# LEDARRAY.net
KiCad netlist of a schematic drawn in EAGLE
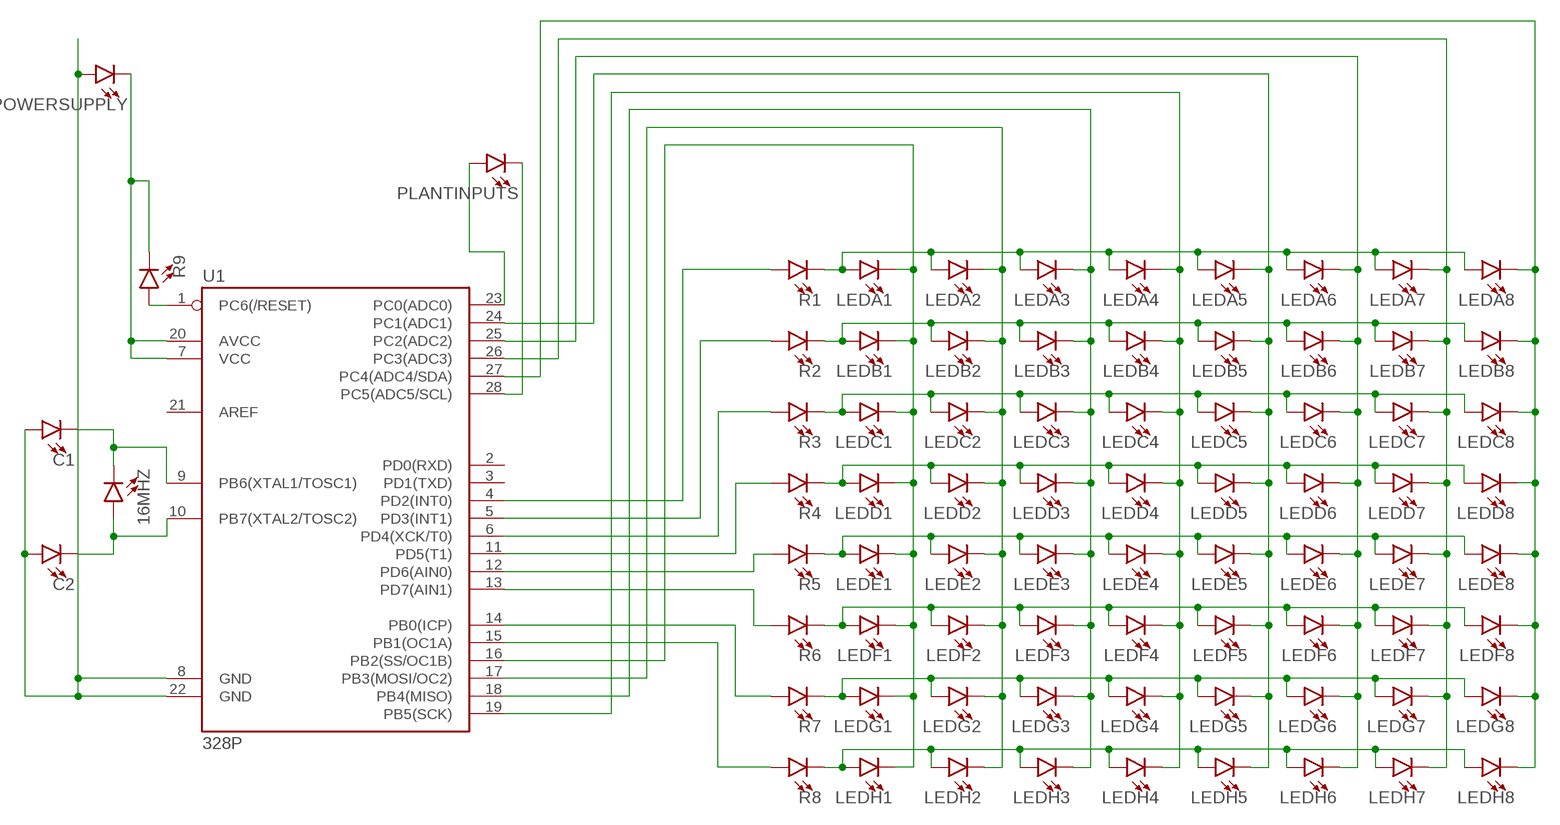
[diagram p0: schematic, sheet 1]

(export (version "E")
  (design (tool "Eeschema 10.0.6"))
  (components
    (comp (ref "16MHZ")
      (value "LED3MM")
      (footprint "eagle-import:LED_3MM")
      (libsource (lib "eagle-import") (part "LED3MM"))
    )
    (comp (ref "C1")
      (value "LED3MM")
      (footprint "eagle-import:LED_3MM")
      (libsource (lib "eagle-import") (part "LED3MM"))
    )
    (comp (ref "C2")
      (value "LED3MM")
      (footprint "eagle-import:LED_3MM")
      (libsource (lib "eagle-import") (part "LED3MM"))
    )
    (comp (ref "LEDA1")
      (value "LED3MM")
      (footprint "eagle-import:LED_3MM")
      (libsource (lib "eagle-import") (part "LED3MM"))
    )
    (comp (ref "LEDA2")
      (value "LED3MM")
      (footprint "eagle-import:LED_3MM")
      (libsource (lib "eagle-import") (part "LED3MM"))
    )
    (comp (ref "LEDA3")
      (value "LED3MM")
      (footprint "eagle-import:LED_3MM")
      (libsource (lib "eagle-import") (part "LED3MM"))
    )
    (comp (ref "LEDA4")
      (value "LED3MM")
      (footprint "eagle-import:LED_3MM")
      (libsource (lib "eagle-import") (part "LED3MM"))
    )
    (comp (ref "LEDA5")
      (value "LED3MM")
      (footprint "eagle-import:LED_3MM")
      (libsource (lib "eagle-import") (part "LED3MM"))
    )
    (comp (ref "LEDA6")
      (value "LED3MM")
      (footprint "eagle-import:LED_3MM")
      (libsource (lib "eagle-import") (part "LED3MM"))
    )
    (comp (ref "LEDA7")
      (value "LED3MM")
      (footprint "eagle-import:LED_3MM")
      (libsource (lib "eagle-import") (part "LED3MM"))
    )
    (comp (ref "LEDA8")
      (value "LED3MM")
      (footprint "eagle-import:LED_3MM")
      (libsource (lib "eagle-import") (part "LED3MM"))
    )
    (comp (ref "LEDB1")
      (value "LED3MM")
      (footprint "eagle-import:LED_3MM")
      (libsource (lib "eagle-import") (part "LED3MM"))
    )
    (comp (ref "LEDB2")
      (value "LED3MM")
      (footprint "eagle-import:LED_3MM")
      (libsource (lib "eagle-import") (part "LED3MM"))
    )
    (comp (ref "LEDB3")
      (value "LED3MM")
      (footprint "eagle-import:LED_3MM")
      (libsource (lib "eagle-import") (part "LED3MM"))
    )
    (comp (ref "LEDB4")
      (value "LED3MM")
      (footprint "eagle-import:LED_3MM")
      (libsource (lib "eagle-import") (part "LED3MM"))
    )
    (comp (ref "LEDB5")
      (value "LED3MM")
      (footprint "eagle-import:LED_3MM")
      (libsource (lib "eagle-import") (part "LED3MM"))
    )
    (comp (ref "LEDB6")
      (value "LED3MM")
      (footprint "eagle-import:LED_3MM")
      (libsource (lib "eagle-import") (part "LED3MM"))
    )
    (comp (ref "LEDB7")
      (value "LED3MM")
      (footprint "eagle-import:LED_3MM")
      (libsource (lib "eagle-import") (part "LED3MM"))
    )
    (comp (ref "LEDB8")
      (value "LED3MM")
      (footprint "eagle-import:LED_3MM")
      (libsource (lib "eagle-import") (part "LED3MM"))
    )
    (comp (ref "LEDC1")
      (value "LED3MM")
      (footprint "eagle-import:LED_3MM")
      (libsource (lib "eagle-import") (part "LED3MM"))
    )
    (comp (ref "LEDC2")
      (value "LED3MM")
      (footprint "eagle-import:LED_3MM")
      (libsource (lib "eagle-import") (part "LED3MM"))
    )
    (comp (ref "LEDC3")
      (value "LED3MM")
      (footprint "eagle-import:LED_3MM")
      (libsource (lib "eagle-import") (part "LED3MM"))
    )
    (comp (ref "LEDC4")
      (value "LED3MM")
      (footprint "eagle-import:LED_3MM")
      (libsource (lib "eagle-import") (part "LED3MM"))
    )
    (comp (ref "LEDC5")
      (value "LED3MM")
      (footprint "eagle-import:LED_3MM")
      (libsource (lib "eagle-import") (part "LED3MM"))
    )
    (comp (ref "LEDC6")
      (value "LED3MM")
      (footprint "eagle-import:LED_3MM")
      (libsource (lib "eagle-import") (part "LED3MM"))
    )
    (comp (ref "LEDC7")
      (value "LED3MM")
      (footprint "eagle-import:LED_3MM")
      (libsource (lib "eagle-import") (part "LED3MM"))
    )
    (comp (ref "LEDC8")
      (value "LED3MM")
      (footprint "eagle-import:LED_3MM")
      (libsource (lib "eagle-import") (part "LED3MM"))
    )
    (comp (ref "LEDD1")
      (value "LED3MM")
      (footprint "eagle-import:LED_3MM")
      (libsource (lib "eagle-import") (part "LED3MM"))
    )
    (comp (ref "LEDD2")
      (value "LED3MM")
      (footprint "eagle-import:LED_3MM")
      (libsource (lib "eagle-import") (part "LED3MM"))
    )
    (comp (ref "LEDD3")
      (value "LED3MM")
      (footprint "eagle-import:LED_3MM")
      (libsource (lib "eagle-import") (part "LED3MM"))
    )
    (comp (ref "LEDD4")
      (value "LED3MM")
      (footprint "eagle-import:LED_3MM")
      (libsource (lib "eagle-import") (part "LED3MM"))
    )
    (comp (ref "LEDD5")
      (value "LED3MM")
      (footprint "eagle-import:LED_3MM")
      (libsource (lib "eagle-import") (part "LED3MM"))
    )
    (comp (ref "LEDD6")
      (value "LED3MM")
      (footprint "eagle-import:LED_3MM")
      (libsource (lib "eagle-import") (part "LED3MM"))
    )
    (comp (ref "LEDD7")
      (value "LED3MM")
      (footprint "eagle-import:LED_3MM")
      (libsource (lib "eagle-import") (part "LED3MM"))
    )
    (comp (ref "LEDD8")
      (value "LED3MM")
      (footprint "eagle-import:LED_3MM")
      (libsource (lib "eagle-import") (part "LED3MM"))
    )
    (comp (ref "LEDE1")
      (value "LED3MM")
      (footprint "eagle-import:LED_3MM")
      (libsource (lib "eagle-import") (part "LED3MM"))
    )
    (comp (ref "LEDE2")
      (value "LED3MM")
      (footprint "eagle-import:LED_3MM")
      (libsource (lib "eagle-import") (part "LED3MM"))
    )
    (comp (ref "LEDE3")
      (value "LED3MM")
      (footprint "eagle-import:LED_3MM")
      (libsource (lib "eagle-import") (part "LED3MM"))
    )
    (comp (ref "LEDE4")
      (value "LED3MM")
      (footprint "eagle-import:LED_3MM")
      (libsource (lib "eagle-import") (part "LED3MM"))
    )
    (comp (ref "LEDE5")
      (value "LED3MM")
      (footprint "eagle-import:LED_3MM")
      (libsource (lib "eagle-import") (part "LED3MM"))
    )
    (comp (ref "LEDE6")
      (value "LED3MM")
      (footprint "eagle-import:LED_3MM")
      (libsource (lib "eagle-import") (part "LED3MM"))
    )
    (comp (ref "LEDE7")
      (value "LED3MM")
      (footprint "eagle-import:LED_3MM")
      (libsource (lib "eagle-import") (part "LED3MM"))
    )
    (comp (ref "LEDE8")
      (value "LED3MM")
      (footprint "eagle-import:LED_3MM")
      (libsource (lib "eagle-import") (part "LED3MM"))
    )
    (comp (ref "LEDF1")
      (value "LED3MM")
      (footprint "eagle-import:LED_3MM")
      (libsource (lib "eagle-import") (part "LED3MM"))
    )
    (comp (ref "LEDF2")
      (value "LED3MM")
      (footprint "eagle-import:LED_3MM")
      (libsource (lib "eagle-import") (part "LED3MM"))
    )
    (comp (ref "LEDF3")
      (value "LED3MM")
      (footprint "eagle-import:LED_3MM")
      (libsource (lib "eagle-import") (part "LED3MM"))
    )
    (comp (ref "LEDF4")
      (value "LED3MM")
      (footprint "eagle-import:LED_3MM")
      (libsource (lib "eagle-import") (part "LED3MM"))
    )
    (comp (ref "LEDF5")
      (value "LED3MM")
      (footprint "eagle-import:LED_3MM")
      (libsource (lib "eagle-import") (part "LED3MM"))
    )
    (comp (ref "LEDF6")
      (value "LED3MM")
      (footprint "eagle-import:LED_3MM")
      (libsource (lib "eagle-import") (part "LED3MM"))
    )
    (comp (ref "LEDF7")
      (value "LED3MM")
      (footprint "eagle-import:LED_3MM")
      (libsource (lib "eagle-import") (part "LED3MM"))
    )
    (comp (ref "LEDF8")
      (value "LED3MM")
      (footprint "eagle-import:LED_3MM")
      (libsource (lib "eagle-import") (part "LED3MM"))
    )
    (comp (ref "LEDG1")
      (value "LED3MM")
      (footprint "eagle-import:LED_3MM")
      (libsource (lib "eagle-import") (part "LED3MM"))
    )
    (comp (ref "LEDG2")
      (value "LED3MM")
      (footprint "eagle-import:LED_3MM")
      (libsource (lib "eagle-import") (part "LED3MM"))
    )
    (comp (ref "LEDG3")
      (value "LED3MM")
      (footprint "eagle-import:LED_3MM")
      (libsource (lib "eagle-import") (part "LED3MM"))
    )
    (comp (ref "LEDG4")
      (value "LED3MM")
      (footprint "eagle-import:LED_3MM")
      (libsource (lib "eagle-import") (part "LED3MM"))
    )
    (comp (ref "LEDG5")
      (value "LED3MM")
      (footprint "eagle-import:LED_3MM")
      (libsource (lib "eagle-import") (part "LED3MM"))
    )
    (comp (ref "LEDG6")
      (value "LED3MM")
      (footprint "eagle-import:LED_3MM")
      (libsource (lib "eagle-import") (part "LED3MM"))
    )
    (comp (ref "LEDG7")
      (value "LED3MM")
      (footprint "eagle-import:LED_3MM")
      (libsource (lib "eagle-import") (part "LED3MM"))
    )
    (comp (ref "LEDG8")
      (value "LED3MM")
      (footprint "eagle-import:LED_3MM")
      (libsource (lib "eagle-import") (part "LED3MM"))
    )
    (comp (ref "LEDH1")
      (value "LED3MM")
      (footprint "eagle-import:LED_3MM")
      (libsource (lib "eagle-import") (part "LED3MM"))
    )
    (comp (ref "LEDH2")
      (value "LED3MM")
      (footprint "eagle-import:LED_3MM")
      (libsource (lib "eagle-import") (part "LED3MM"))
    )
    (comp (ref "LEDH3")
      (value "LED3MM")
      (footprint "eagle-import:LED_3MM")
      (libsource (lib "eagle-import") (part "LED3MM"))
    )
    (comp (ref "LEDH4")
      (value "LED3MM")
      (footprint "eagle-import:LED_3MM")
      (libsource (lib "eagle-import") (part "LED3MM"))
    )
    (comp (ref "LEDH5")
      (value "LED3MM")
      (footprint "eagle-import:LED_3MM")
      (libsource (lib "eagle-import") (part "LED3MM"))
    )
    (comp (ref "LEDH6")
      (value "LED3MM")
      (footprint "eagle-import:LED_3MM")
      (libsource (lib "eagle-import") (part "LED3MM"))
    )
    (comp (ref "LEDH7")
      (value "LED3MM")
      (footprint "eagle-import:LED_3MM")
      (libsource (lib "eagle-import") (part "LED3MM"))
    )
    (comp (ref "LEDH8")
      (value "LED3MM")
      (footprint "eagle-import:LED_3MM")
      (libsource (lib "eagle-import") (part "LED3MM"))
    )
    (comp (ref "PLANTINPUTS")
      (value "LED3MM")
      (footprint "eagle-import:LED_3MM")
      (libsource (lib "eagle-import") (part "LED3MM"))
    )
    (comp (ref "POWERSUPPLY")
      (value "LED3MM")
      (footprint "eagle-import:LED_3MM")
      (libsource (lib "eagle-import") (part "LED3MM"))
    )
    (comp (ref "R1")
      (value "LED3MM")
      (footprint "eagle-import:LED_3MM")
      (libsource (lib "eagle-import") (part "LED3MM"))
    )
    (comp (ref "R2")
      (value "LED3MM")
      (footprint "eagle-import:LED_3MM")
      (libsource (lib "eagle-import") (part "LED3MM"))
    )
    (comp (ref "R3")
      (value "LED3MM")
      (footprint "eagle-import:LED_3MM")
      (libsource (lib "eagle-import") (part "LED3MM"))
    )
    (comp (ref "R4")
      (value "LED3MM")
      (footprint "eagle-import:LED_3MM")
      (libsource (lib "eagle-import") (part "LED3MM"))
    )
    (comp (ref "R5")
      (value "LED3MM")
      (footprint "eagle-import:LED_3MM")
      (libsource (lib "eagle-import") (part "LED3MM"))
    )
    (comp (ref "R6")
      (value "LED3MM")
      (footprint "eagle-import:LED_3MM")
      (libsource (lib "eagle-import") (part "LED3MM"))
    )
    (comp (ref "R7")
      (value "LED3MM")
      (footprint "eagle-import:LED_3MM")
      (libsource (lib "eagle-import") (part "LED3MM"))
    )
    (comp (ref "R8")
      (value "LED3MM")
      (footprint "eagle-import:LED_3MM")
      (libsource (lib "eagle-import") (part "LED3MM"))
    )
    (comp (ref "R9")
      (value "LED3MM")
      (footprint "eagle-import:LED_3MM")
      (libsource (lib "eagle-import") (part "LED3MM"))
    )
    (comp (ref "U1")
      (value "328P")
      (footprint "eagle-import:DIP28")
      (libsource (lib "eagle-import") (part "ATMEGA328P_PDIP"))
    )
  )
  (nets
    (net (code "1") (name "Net-(16MHZ-C)") (class "Default")
      (node (ref "16MHZ") (pin "K") (pinfunction "C_K") (pintype "passive"))
      (node (ref "C1") (pin "K") (pinfunction "C_K") (pintype "passive"))
      (node (ref "U1") (pin "9") (pinfunction "PB6(XTAL1/TOSC1)_9") (pintype "bidirectional"))
    )
    (net (code "2") (name "Net-(C1-PadA)") (class "Default")
      (node (ref "C1") (pin "A") (pinfunction "A_A") (pintype "passive"))
      (node (ref "C2") (pin "A") (pinfunction "A_A") (pintype "passive"))
      (node (ref "POWERSUPPLY") (pin "A") (pinfunction "A_A") (pintype "passive"))
      (node (ref "U1") (pin "22") (pinfunction "GND_22") (pintype "bidirectional"))
      (node (ref "U1") (pin "8") (pinfunction "GND_8") (pintype "bidirectional"))
    )
    (net (code "3") (name "Net-(C2-C)") (class "Default")
      (node (ref "16MHZ") (pin "A") (pinfunction "A_A") (pintype "passive"))
      (node (ref "C2") (pin "K") (pinfunction "C_K") (pintype "passive"))
      (node (ref "U1") (pin "10") (pinfunction "PB7(XTAL2/TOSC2)_10") (pintype "bidirectional"))
    )
    (net (code "4") (name "Net-(LEDA1-C)") (class "Default")
      (node (ref "LEDA1") (pin "K") (pinfunction "C_K") (pintype "passive"))
      (node (ref "LEDB1") (pin "K") (pinfunction "C_K") (pintype "passive"))
      (node (ref "LEDC1") (pin "K") (pinfunction "C_K") (pintype "passive"))
      (node (ref "LEDD1") (pin "K") (pinfunction "C_K") (pintype "passive"))
      (node (ref "LEDE1") (pin "K") (pinfunction "C_K") (pintype "passive"))
      (node (ref "LEDF1") (pin "K") (pinfunction "C_K") (pintype "passive"))
      (node (ref "LEDG1") (pin "K") (pinfunction "C_K") (pintype "passive"))
      (node (ref "LEDH1") (pin "K") (pinfunction "C_K") (pintype "passive"))
      (node (ref "U1") (pin "16") (pinfunction "PB2(SS/OC1B)_16") (pintype "bidirectional"))
    )
    (net (code "5") (name "Net-(LEDA2-C)") (class "Default")
      (node (ref "LEDA2") (pin "K") (pinfunction "C_K") (pintype "passive"))
      (node (ref "LEDB2") (pin "K") (pinfunction "C_K") (pintype "passive"))
      (node (ref "LEDC2") (pin "K") (pinfunction "C_K") (pintype "passive"))
      (node (ref "LEDD2") (pin "K") (pinfunction "C_K") (pintype "passive"))
      (node (ref "LEDE2") (pin "K") (pinfunction "C_K") (pintype "passive"))
      (node (ref "LEDF2") (pin "K") (pinfunction "C_K") (pintype "passive"))
      (node (ref "LEDG2") (pin "K") (pinfunction "C_K") (pintype "passive"))
      (node (ref "LEDH2") (pin "K") (pinfunction "C_K") (pintype "passive"))
      (node (ref "U1") (pin "17") (pinfunction "PB3(MOSI/OC2)_17") (pintype "bidirectional"))
    )
    (net (code "6") (name "Net-(LEDA3-C)") (class "Default")
      (node (ref "LEDA3") (pin "K") (pinfunction "C_K") (pintype "passive"))
      (node (ref "LEDB3") (pin "K") (pinfunction "C_K") (pintype "passive"))
      (node (ref "LEDC3") (pin "K") (pinfunction "C_K") (pintype "passive"))
      (node (ref "LEDD3") (pin "K") (pinfunction "C_K") (pintype "passive"))
      (node (ref "LEDE3") (pin "K") (pinfunction "C_K") (pintype "passive"))
      (node (ref "LEDF3") (pin "K") (pinfunction "C_K") (pintype "passive"))
      (node (ref "LEDG3") (pin "K") (pinfunction "C_K") (pintype "passive"))
      (node (ref "LEDH3") (pin "K") (pinfunction "C_K") (pintype "passive"))
      (node (ref "U1") (pin "18") (pinfunction "PB4(MISO)_18") (pintype "bidirectional"))
    )
    (net (code "7") (name "Net-(LEDA4-C)") (class "Default")
      (node (ref "LEDA4") (pin "K") (pinfunction "C_K") (pintype "passive"))
      (node (ref "LEDB4") (pin "K") (pinfunction "C_K") (pintype "passive"))
      (node (ref "LEDC4") (pin "K") (pinfunction "C_K") (pintype "passive"))
      (node (ref "LEDD4") (pin "K") (pinfunction "C_K") (pintype "passive"))
      (node (ref "LEDE4") (pin "K") (pinfunction "C_K") (pintype "passive"))
      (node (ref "LEDF4") (pin "K") (pinfunction "C_K") (pintype "passive"))
      (node (ref "LEDG4") (pin "K") (pinfunction "C_K") (pintype "passive"))
      (node (ref "LEDH4") (pin "K") (pinfunction "C_K") (pintype "passive"))
      (node (ref "U1") (pin "19") (pinfunction "PB5(SCK)_19") (pintype "bidirectional"))
    )
    (net (code "8") (name "Net-(LEDA5-C)") (class "Default")
      (node (ref "LEDA5") (pin "K") (pinfunction "C_K") (pintype "passive"))
      (node (ref "LEDB5") (pin "K") (pinfunction "C_K") (pintype "passive"))
      (node (ref "LEDC5") (pin "K") (pinfunction "C_K") (pintype "passive"))
      (node (ref "LEDD5") (pin "K") (pinfunction "C_K") (pintype "passive"))
      (node (ref "LEDE5") (pin "K") (pinfunction "C_K") (pintype "passive"))
      (node (ref "LEDF5") (pin "K") (pinfunction "C_K") (pintype "passive"))
      (node (ref "LEDG5") (pin "K") (pinfunction "C_K") (pintype "passive"))
      (node (ref "LEDH5") (pin "K") (pinfunction "C_K") (pintype "passive"))
      (node (ref "U1") (pin "24") (pinfunction "PC1(ADC1)_24") (pintype "bidirectional"))
    )
    (net (code "9") (name "Net-(LEDA6-C)") (class "Default")
      (node (ref "LEDA6") (pin "K") (pinfunction "C_K") (pintype "passive"))
      (node (ref "LEDB6") (pin "K") (pinfunction "C_K") (pintype "passive"))
      (node (ref "LEDC6") (pin "K") (pinfunction "C_K") (pintype "passive"))
      (node (ref "LEDD6") (pin "K") (pinfunction "C_K") (pintype "passive"))
      (node (ref "LEDE6") (pin "K") (pinfunction "C_K") (pintype "passive"))
      (node (ref "LEDF6") (pin "K") (pinfunction "C_K") (pintype "passive"))
      (node (ref "LEDG6") (pin "K") (pinfunction "C_K") (pintype "passive"))
      (node (ref "LEDH6") (pin "K") (pinfunction "C_K") (pintype "passive"))
      (node (ref "U1") (pin "25") (pinfunction "PC2(ADC2)_25") (pintype "bidirectional"))
    )
    (net (code "10") (name "Net-(LEDA7-C)") (class "Default")
      (node (ref "LEDA7") (pin "K") (pinfunction "C_K") (pintype "passive"))
      (node (ref "LEDB7") (pin "K") (pinfunction "C_K") (pintype "passive"))
      (node (ref "LEDC7") (pin "K") (pinfunction "C_K") (pintype "passive"))
      (node (ref "LEDD7") (pin "K") (pinfunction "C_K") (pintype "passive"))
      (node (ref "LEDE7") (pin "K") (pinfunction "C_K") (pintype "passive"))
      (node (ref "LEDF7") (pin "K") (pinfunction "C_K") (pintype "passive"))
      (node (ref "LEDG7") (pin "K") (pinfunction "C_K") (pintype "passive"))
      (node (ref "LEDH7") (pin "K") (pinfunction "C_K") (pintype "passive"))
      (node (ref "U1") (pin "26") (pinfunction "PC3(ADC3)_26") (pintype "bidirectional"))
    )
    (net (code "11") (name "Net-(LEDA8-C)") (class "Default")
      (node (ref "LEDA8") (pin "K") (pinfunction "C_K") (pintype "passive"))
      (node (ref "LEDB8") (pin "K") (pinfunction "C_K") (pintype "passive"))
      (node (ref "LEDC8") (pin "K") (pinfunction "C_K") (pintype "passive"))
      (node (ref "LEDD8") (pin "K") (pinfunction "C_K") (pintype "passive"))
      (node (ref "LEDE8") (pin "K") (pinfunction "C_K") (pintype "passive"))
      (node (ref "LEDF8") (pin "K") (pinfunction "C_K") (pintype "passive"))
      (node (ref "LEDG8") (pin "K") (pinfunction "C_K") (pintype "passive"))
      (node (ref "LEDH8") (pin "K") (pinfunction "C_K") (pintype "passive"))
      (node (ref "U1") (pin "27") (pinfunction "PC4(ADC4/SDA)_27") (pintype "bidirectional"))
    )
    (net (code "12") (name "Net-(PLANTINPUTS-C)") (class "Default")
      (node (ref "PLANTINPUTS") (pin "K") (pinfunction "C_K") (pintype "passive"))
      (node (ref "U1") (pin "28") (pinfunction "PC5(ADC5/SCL)_28") (pintype "bidirectional"))
    )
    (net (code "13") (name "Net-(POWERSUPPLY-C)") (class "Default")
      (node (ref "POWERSUPPLY") (pin "K") (pinfunction "C_K") (pintype "passive"))
      (node (ref "R9") (pin "K") (pinfunction "C_K") (pintype "passive"))
      (node (ref "U1") (pin "20") (pinfunction "AVCC_20") (pintype "bidirectional"))
      (node (ref "U1") (pin "7") (pinfunction "VCC_7") (pintype "bidirectional"))
    )
    (net (code "14") (name "Net-(R1-C)") (class "Default")
      (node (ref "LEDA1") (pin "A") (pinfunction "A_A") (pintype "passive"))
      (node (ref "LEDA2") (pin "A") (pinfunction "A_A") (pintype "passive"))
      (node (ref "LEDA3") (pin "A") (pinfunction "A_A") (pintype "passive"))
      (node (ref "LEDA4") (pin "A") (pinfunction "A_A") (pintype "passive"))
      (node (ref "LEDA5") (pin "A") (pinfunction "A_A") (pintype "passive"))
      (node (ref "LEDA6") (pin "A") (pinfunction "A_A") (pintype "passive"))
      (node (ref "LEDA7") (pin "A") (pinfunction "A_A") (pintype "passive"))
      (node (ref "LEDA8") (pin "A") (pinfunction "A_A") (pintype "passive"))
      (node (ref "R1") (pin "K") (pinfunction "C_K") (pintype "passive"))
    )
    (net (code "15") (name "Net-(R2-C)") (class "Default")
      (node (ref "LEDB1") (pin "A") (pinfunction "A_A") (pintype "passive"))
      (node (ref "LEDB2") (pin "A") (pinfunction "A_A") (pintype "passive"))
      (node (ref "LEDB3") (pin "A") (pinfunction "A_A") (pintype "passive"))
      (node (ref "LEDB4") (pin "A") (pinfunction "A_A") (pintype "passive"))
      (node (ref "LEDB5") (pin "A") (pinfunction "A_A") (pintype "passive"))
      (node (ref "LEDB6") (pin "A") (pinfunction "A_A") (pintype "passive"))
      (node (ref "LEDB7") (pin "A") (pinfunction "A_A") (pintype "passive"))
      (node (ref "LEDB8") (pin "A") (pinfunction "A_A") (pintype "passive"))
      (node (ref "R2") (pin "K") (pinfunction "C_K") (pintype "passive"))
    )
    (net (code "16") (name "Net-(R3-C)") (class "Default")
      (node (ref "LEDC1") (pin "A") (pinfunction "A_A") (pintype "passive"))
      (node (ref "LEDC2") (pin "A") (pinfunction "A_A") (pintype "passive"))
      (node (ref "LEDC3") (pin "A") (pinfunction "A_A") (pintype "passive"))
      (node (ref "LEDC4") (pin "A") (pinfunction "A_A") (pintype "passive"))
      (node (ref "LEDC5") (pin "A") (pinfunction "A_A") (pintype "passive"))
      (node (ref "LEDC6") (pin "A") (pinfunction "A_A") (pintype "passive"))
      (node (ref "LEDC7") (pin "A") (pinfunction "A_A") (pintype "passive"))
      (node (ref "LEDC8") (pin "A") (pinfunction "A_A") (pintype "passive"))
      (node (ref "R3") (pin "K") (pinfunction "C_K") (pintype "passive"))
    )
    (net (code "17") (name "Net-(R4-C)") (class "Default")
      (node (ref "LEDD1") (pin "A") (pinfunction "A_A") (pintype "passive"))
      (node (ref "LEDD2") (pin "A") (pinfunction "A_A") (pintype "passive"))
      (node (ref "LEDD3") (pin "A") (pinfunction "A_A") (pintype "passive"))
      (node (ref "LEDD4") (pin "A") (pinfunction "A_A") (pintype "passive"))
      (node (ref "LEDD5") (pin "A") (pinfunction "A_A") (pintype "passive"))
      (node (ref "LEDD6") (pin "A") (pinfunction "A_A") (pintype "passive"))
      (node (ref "LEDD7") (pin "A") (pinfunction "A_A") (pintype "passive"))
      (node (ref "LEDD8") (pin "A") (pinfunction "A_A") (pintype "passive"))
      (node (ref "R4") (pin "K") (pinfunction "C_K") (pintype "passive"))
    )
    (net (code "18") (name "Net-(R5-C)") (class "Default")
      (node (ref "LEDE1") (pin "A") (pinfunction "A_A") (pintype "passive"))
      (node (ref "LEDE2") (pin "A") (pinfunction "A_A") (pintype "passive"))
      (node (ref "LEDE3") (pin "A") (pinfunction "A_A") (pintype "passive"))
      (node (ref "LEDE4") (pin "A") (pinfunction "A_A") (pintype "passive"))
      (node (ref "LEDE5") (pin "A") (pinfunction "A_A") (pintype "passive"))
      (node (ref "LEDE6") (pin "A") (pinfunction "A_A") (pintype "passive"))
      (node (ref "LEDE7") (pin "A") (pinfunction "A_A") (pintype "passive"))
      (node (ref "LEDE8") (pin "A") (pinfunction "A_A") (pintype "passive"))
      (node (ref "R5") (pin "K") (pinfunction "C_K") (pintype "passive"))
    )
    (net (code "19") (name "Net-(R6-C)") (class "Default")
      (node (ref "LEDF1") (pin "A") (pinfunction "A_A") (pintype "passive"))
      (node (ref "LEDF2") (pin "A") (pinfunction "A_A") (pintype "passive"))
      (node (ref "LEDF3") (pin "A") (pinfunction "A_A") (pintype "passive"))
      (node (ref "LEDF4") (pin "A") (pinfunction "A_A") (pintype "passive"))
      (node (ref "LEDF5") (pin "A") (pinfunction "A_A") (pintype "passive"))
      (node (ref "LEDF6") (pin "A") (pinfunction "A_A") (pintype "passive"))
      (node (ref "LEDF7") (pin "A") (pinfunction "A_A") (pintype "passive"))
      (node (ref "LEDF8") (pin "A") (pinfunction "A_A") (pintype "passive"))
      (node (ref "R6") (pin "K") (pinfunction "C_K") (pintype "passive"))
    )
    (net (code "20") (name "Net-(R7-C)") (class "Default")
      (node (ref "LEDG1") (pin "A") (pinfunction "A_A") (pintype "passive"))
      (node (ref "LEDG2") (pin "A") (pinfunction "A_A") (pintype "passive"))
      (node (ref "LEDG3") (pin "A") (pinfunction "A_A") (pintype "passive"))
      (node (ref "LEDG4") (pin "A") (pinfunction "A_A") (pintype "passive"))
      (node (ref "LEDG5") (pin "A") (pinfunction "A_A") (pintype "passive"))
      (node (ref "LEDG6") (pin "A") (pinfunction "A_A") (pintype "passive"))
      (node (ref "LEDG7") (pin "A") (pinfunction "A_A") (pintype "passive"))
      (node (ref "LEDG8") (pin "A") (pinfunction "A_A") (pintype "passive"))
      (node (ref "R7") (pin "K") (pinfunction "C_K") (pintype "passive"))
    )
    (net (code "21") (name "Net-(R8-C)") (class "Default")
      (node (ref "LEDH1") (pin "A") (pinfunction "A_A") (pintype "passive"))
      (node (ref "LEDH2") (pin "A") (pinfunction "A_A") (pintype "passive"))
      (node (ref "LEDH3") (pin "A") (pinfunction "A_A") (pintype "passive"))
      (node (ref "LEDH4") (pin "A") (pinfunction "A_A") (pintype "passive"))
      (node (ref "LEDH5") (pin "A") (pinfunction "A_A") (pintype "passive"))
      (node (ref "LEDH6") (pin "A") (pinfunction "A_A") (pintype "passive"))
      (node (ref "LEDH7") (pin "A") (pinfunction "A_A") (pintype "passive"))
      (node (ref "LEDH8") (pin "A") (pinfunction "A_A") (pintype "passive"))
      (node (ref "R8") (pin "K") (pinfunction "C_K") (pintype "passive"))
    )
    (net (code "22") (name "Net-(U1-PB0(ICP))") (class "Default")
      (node (ref "R7") (pin "A") (pinfunction "A_A") (pintype "passive"))
      (node (ref "U1") (pin "14") (pinfunction "PB0(ICP)_14") (pintype "bidirectional"))
    )
    (net (code "23") (name "Net-(U1-PB1(OC1A))") (class "Default")
      (node (ref "R8") (pin "A") (pinfunction "A_A") (pintype "passive"))
      (node (ref "U1") (pin "15") (pinfunction "PB1(OC1A)_15") (pintype "bidirectional"))
    )
    (net (code "24") (name "Net-(U1-PC0(ADC0))") (class "Default")
      (node (ref "PLANTINPUTS") (pin "A") (pinfunction "A_A") (pintype "passive"))
      (node (ref "U1") (pin "23") (pinfunction "PC0(ADC0)_23") (pintype "bidirectional"))
    )
    (net (code "25") (name "Net-(U1-PC6({slash}RESET))") (class "Default")
      (node (ref "R9") (pin "A") (pinfunction "A_A") (pintype "passive"))
      (node (ref "U1") (pin "1") (pinfunction "PC6(/RESET)_1") (pintype "bidirectional"))
    )
    (net (code "26") (name "Net-(U1-PD2(INT0))") (class "Default")
      (node (ref "R1") (pin "A") (pinfunction "A_A") (pintype "passive"))
      (node (ref "U1") (pin "4") (pinfunction "PD2(INT0)_4") (pintype "bidirectional"))
    )
    (net (code "27") (name "Net-(U1-PD3(INT1))") (class "Default")
      (node (ref "R2") (pin "A") (pinfunction "A_A") (pintype "passive"))
      (node (ref "U1") (pin "5") (pinfunction "PD3(INT1)_5") (pintype "bidirectional"))
    )
    (net (code "28") (name "Net-(U1-PD4(XCK{slash}T0))") (class "Default")
      (node (ref "R3") (pin "A") (pinfunction "A_A") (pintype "passive"))
      (node (ref "U1") (pin "6") (pinfunction "PD4(XCK/T0)_6") (pintype "bidirectional"))
    )
    (net (code "29") (name "Net-(U1-PD5(T1))") (class "Default")
      (node (ref "R4") (pin "A") (pinfunction "A_A") (pintype "passive"))
      (node (ref "U1") (pin "11") (pinfunction "PD5(T1)_11") (pintype "bidirectional"))
    )
    (net (code "30") (name "Net-(U1-PD6(AIN0))") (class "Default")
      (node (ref "R5") (pin "A") (pinfunction "A_A") (pintype "passive"))
      (node (ref "U1") (pin "12") (pinfunction "PD6(AIN0)_12") (pintype "bidirectional"))
    )
    (net (code "31") (name "Net-(U1-PD7(AIN1))") (class "Default")
      (node (ref "R6") (pin "A") (pinfunction "A_A") (pintype "passive"))
      (node (ref "U1") (pin "13") (pinfunction "PD7(AIN1)_13") (pintype "bidirectional"))
    )
    (net (code "32") (name "unconnected-(U1-AREF-Pad21)") (class "Default")
      (node (ref "U1") (pin "21") (pinfunction "AREF_21") (pintype "bidirectional"))
    )
    (net (code "33") (name "unconnected-(U1-PD0(RXD)-Pad2)") (class "Default")
      (node (ref "U1") (pin "2") (pinfunction "PD0(RXD)_2") (pintype "bidirectional"))
    )
    (net (code "34") (name "unconnected-(U1-PD1(TXD)-Pad3)") (class "Default")
      (node (ref "U1") (pin "3") (pinfunction "PD1(TXD)_3") (pintype "bidirectional"))
    )
  )
)
